# ESP-Power.net
KiCad netlist of a schematic drawn in Altium Designer
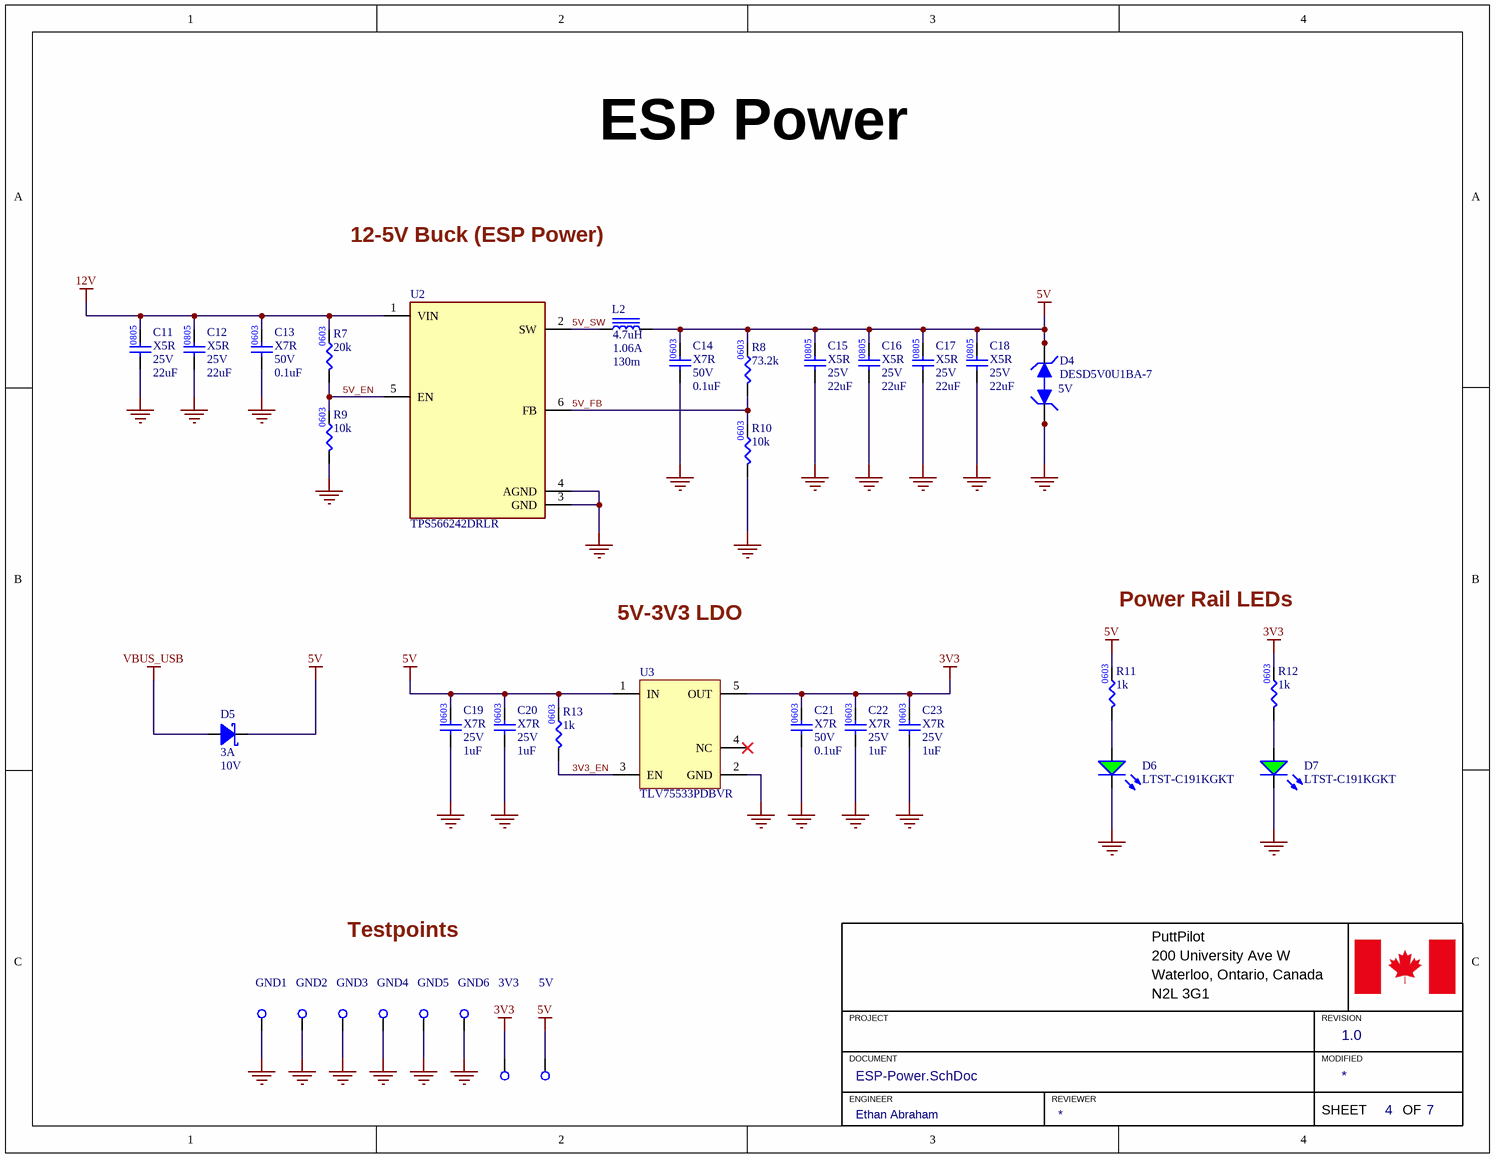
[diagram p0: ESP-Power.SchDoc]

(export (version "E")
  (design (tool "Eeschema 10.0.6"))
  (components
    (comp (ref "3V3")
      (value "RCWCTE")
      (footprint "RCWCTE")
      (description "SMT Test Point")
      (fields (field (name "MANUFACTURER") "KOA Speer"))
      (libsource (lib "PuttPilot") (part "RCWCTE"))
    )
    (comp (ref "5V")
      (value "RCWCTE")
      (footprint "RCWCTE")
      (description "SMT Test Point")
      (fields (field (name "MANUFACTURER") "KOA Speer"))
      (libsource (lib "PuttPilot") (part "RCWCTE"))
    )
    (comp (ref "C11")
      (value "GRM21BR61E226ME44K")
      (footprint ".CAP_0805")
      (description "CAP CER 22uF 25V X5R 0805")
      (fields
        (field (name "MANUFACTURER") "Murata")
        (field (name "TEMPERATURE CHARACTERISTICS CODE") "X5R")
        (field (name "RATED DC VOLTAGE (URDC)") "25V")
        (field (name "CAPACITANCE") "22uF")
      )
      (libsource (lib "PuttPilot") (part "GRM21BR61E226ME44K"))
    )
    (comp (ref "C12")
      (value "GRM21BR61E226ME44K")
      (footprint ".CAP_0805")
      (description "CAP CER 22uF 25V X5R 0805")
      (fields
        (field (name "MANUFACTURER") "Murata")
        (field (name "TEMPERATURE CHARACTERISTICS CODE") "X5R")
        (field (name "RATED DC VOLTAGE (URDC)") "25V")
        (field (name "CAPACITANCE") "22uF")
      )
      (libsource (lib "PuttPilot") (part "GRM21BR61E226ME44K"))
    )
    (comp (ref "C13")
      (value "GCJ188R71H104KA12D")
      (footprint ".CAP_0603")
      (description "CAP CER 0.1uF 50V X7R 0603")
      (fields
        (field (name "MANUFACTURER") "Murata")
        (field (name "TEMPERATURE CHARACTERISTICS CODE") "X7R")
        (field (name "RATED DC VOLTAGE (URDC)") "50V")
        (field (name "CAPACITANCE") "0.1uF")
      )
      (libsource (lib "PuttPilot") (part "GCJ188R71H104KA12D"))
    )
    (comp (ref "C14")
      (value "GCJ188R71H104KA12D")
      (footprint ".CAP_0603")
      (description "CAP CER 0.1uF 50V X7R 0603")
      (fields
        (field (name "MANUFACTURER") "Murata")
        (field (name "TEMPERATURE CHARACTERISTICS CODE") "X7R")
        (field (name "RATED DC VOLTAGE (URDC)") "50V")
        (field (name "CAPACITANCE") "0.1uF")
      )
      (libsource (lib "PuttPilot") (part "GCJ188R71H104KA12D"))
    )
    (comp (ref "C15")
      (value "GRM21BR61E226ME44K")
      (footprint ".CAP_0805")
      (description "CAP CER 22uF 25V X5R 0805")
      (fields
        (field (name "MANUFACTURER") "Murata")
        (field (name "TEMPERATURE CHARACTERISTICS CODE") "X5R")
        (field (name "RATED DC VOLTAGE (URDC)") "25V")
        (field (name "CAPACITANCE") "22uF")
      )
      (libsource (lib "PuttPilot") (part "GRM21BR61E226ME44K"))
    )
    (comp (ref "C16")
      (value "GRM21BR61E226ME44K")
      (footprint ".CAP_0805")
      (description "CAP CER 22uF 25V X5R 0805")
      (fields
        (field (name "MANUFACTURER") "Murata")
        (field (name "TEMPERATURE CHARACTERISTICS CODE") "X5R")
        (field (name "RATED DC VOLTAGE (URDC)") "25V")
        (field (name "CAPACITANCE") "22uF")
      )
      (libsource (lib "PuttPilot") (part "GRM21BR61E226ME44K"))
    )
    (comp (ref "C17")
      (value "GRM21BR61E226ME44K")
      (footprint ".CAP_0805")
      (description "CAP CER 22uF 25V X5R 0805")
      (fields
        (field (name "MANUFACTURER") "Murata")
        (field (name "TEMPERATURE CHARACTERISTICS CODE") "X5R")
        (field (name "RATED DC VOLTAGE (URDC)") "25V")
        (field (name "CAPACITANCE") "22uF")
      )
      (libsource (lib "PuttPilot") (part "GRM21BR61E226ME44K"))
    )
    (comp (ref "C18")
      (value "GRM21BR61E226ME44K")
      (footprint ".CAP_0805")
      (description "CAP CER 22uF 25V X5R 0805")
      (fields
        (field (name "MANUFACTURER") "Murata")
        (field (name "TEMPERATURE CHARACTERISTICS CODE") "X5R")
        (field (name "RATED DC VOLTAGE (URDC)") "25V")
        (field (name "CAPACITANCE") "22uF")
      )
      (libsource (lib "PuttPilot") (part "GRM21BR61E226ME44K"))
    )
    (comp (ref "C19")
      (value "GRT188R71E105KE13D")
      (footprint ".CAP_0603")
      (description "CAP CER 1uF 25V X7R 0603")
      (fields
        (field (name "MANUFACTURER") "Murata")
        (field (name "TEMPERATURE CHARACTERISTICS CODE") "X7R")
        (field (name "RATED DC VOLTAGE (URDC)") "25V")
        (field (name "CAPACITANCE") "1uF")
      )
      (libsource (lib "PuttPilot") (part "GRT188R71E105KE13D"))
    )
    (comp (ref "C20")
      (value "GRT188R71E105KE13D")
      (footprint ".CAP_0603")
      (description "CAP CER 1uF 25V X7R 0603")
      (fields
        (field (name "MANUFACTURER") "Murata")
        (field (name "TEMPERATURE CHARACTERISTICS CODE") "X7R")
        (field (name "RATED DC VOLTAGE (URDC)") "25V")
        (field (name "CAPACITANCE") "1uF")
      )
      (libsource (lib "PuttPilot") (part "GRT188R71E105KE13D"))
    )
    (comp (ref "C21")
      (value "GCJ188R71H104KA12D")
      (footprint ".CAP_0603")
      (description "CAP CER 0.1uF 50V X7R 0603")
      (fields
        (field (name "MANUFACTURER") "Murata")
        (field (name "TEMPERATURE CHARACTERISTICS CODE") "X7R")
        (field (name "RATED DC VOLTAGE (URDC)") "50V")
        (field (name "CAPACITANCE") "0.1uF")
      )
      (libsource (lib "PuttPilot") (part "GCJ188R71H104KA12D"))
    )
    (comp (ref "C22")
      (value "GRT188R71E105KE13D")
      (footprint ".CAP_0603")
      (description "CAP CER 1uF 25V X7R 0603")
      (fields
        (field (name "MANUFACTURER") "Murata")
        (field (name "TEMPERATURE CHARACTERISTICS CODE") "X7R")
        (field (name "RATED DC VOLTAGE (URDC)") "25V")
        (field (name "CAPACITANCE") "1uF")
      )
      (libsource (lib "PuttPilot") (part "GRT188R71E105KE13D"))
    )
    (comp (ref "C23")
      (value "GRT188R71E105KE13D")
      (footprint ".CAP_0603")
      (description "CAP CER 1uF 25V X7R 0603")
      (fields
        (field (name "MANUFACTURER") "Murata")
        (field (name "TEMPERATURE CHARACTERISTICS CODE") "X7R")
        (field (name "RATED DC VOLTAGE (URDC)") "25V")
        (field (name "CAPACITANCE") "1uF")
      )
      (libsource (lib "PuttPilot") (part "GRT188R71E105KE13D"))
    )
    (comp (ref "D4")
      (value "DESD5V0U1BA-7")
      (footprint "DESD5V0U1BA-7")
      (description "TVS DIODE 5VWM")
      (fields (field (name "MANUFACTURER") "Diodes") (field (name "REP PK REVERSE VOLTAGE-MAX") "5V"))
      (libsource (lib "PuttPilot") (part "DESD5V0U1BA-7"))
    )
    (comp (ref "D5")
      (value "BAT60JFILM")
      (footprint "BAT60JFILM")
      (description "DIODE SCHOTTKY 10V 3A SOD323")
      (fields (field (name "MAX CURRENT") "3A") (field (name "MAX VOLTAGE") "10V"))
      (libsource (lib "PuttPilot") (part "BAT60JFILM"))
    )
    (comp (ref "D6")
      (value "LTST-C191KGKT")
      (footprint ".LED_0603")
      (description "LED GREEN 2V 0603")
      (fields (field (name "MANUFACTURER") "Vishay Lite-On"))
      (libsource (lib "PuttPilot") (part "LTST-C191KGKT"))
    )
    (comp (ref "D7")
      (value "LTST-C191KGKT")
      (footprint ".LED_0603")
      (description "LED GREEN 2V 0603")
      (fields (field (name "MANUFACTURER") "Vishay Lite-On"))
      (libsource (lib "PuttPilot") (part "LTST-C191KGKT"))
    )
    (comp (ref "GND1")
      (value "RCWCTE")
      (footprint "RCWCTE")
      (description "SMT Test Point")
      (fields (field (name "MANUFACTURER") "KOA Speer"))
      (libsource (lib "PuttPilot") (part "RCWCTE"))
    )
    (comp (ref "GND2")
      (value "RCWCTE")
      (footprint "RCWCTE")
      (description "SMT Test Point")
      (fields (field (name "MANUFACTURER") "KOA Speer"))
      (libsource (lib "PuttPilot") (part "RCWCTE"))
    )
    (comp (ref "GND3")
      (value "RCWCTE")
      (footprint "RCWCTE")
      (description "SMT Test Point")
      (fields (field (name "MANUFACTURER") "KOA Speer"))
      (libsource (lib "PuttPilot") (part "RCWCTE"))
    )
    (comp (ref "GND4")
      (value "RCWCTE")
      (footprint "RCWCTE")
      (description "SMT Test Point")
      (fields (field (name "MANUFACTURER") "KOA Speer"))
      (libsource (lib "PuttPilot") (part "RCWCTE"))
    )
    (comp (ref "GND5")
      (value "RCWCTE")
      (footprint "RCWCTE")
      (description "SMT Test Point")
      (fields (field (name "MANUFACTURER") "KOA Speer"))
      (libsource (lib "PuttPilot") (part "RCWCTE"))
    )
    (comp (ref "GND6")
      (value "RCWCTE")
      (footprint "RCWCTE")
      (description "SMT Test Point")
      (fields (field (name "MANUFACTURER") "KOA Speer"))
      (libsource (lib "PuttPilot") (part "RCWCTE"))
    )
    (comp (ref "L2")
      (value "NRH3012T4R7MN")
      (footprint "NRH3012T4R7MN")
      (description "FIXED IND 4.7uH 1.06A")
      (fields
        (field (name "MANUFACTURER") "Taiyo Yuden")
        (field (name "TOLERANCE") "20%")
        (field (name "DC RESISTANCE (DCR)") "130m")
        (field (name "INDUCTANCE-NOM (L)") "4.7uH")
        (field (name "RATED CURRENT-MAX") "1.06A")
      )
      (libsource (lib "PuttPilot") (part "NRH3012T4R7MN"))
    )
    (comp (ref "R7")
      (value "ERJ-3EKF2002V")
      (footprint ".RES_0603")
      (description "RES 20K OHM 0603")
      (fields
        (field (name "MANUFACTURER") "Panasonic")
        (field (name "TOLERANCE") "1%")
        (field (name "RESISTANCE") "20k")
      )
      (libsource (lib "PuttPilot") (part "ERJ-3EKF2002V"))
    )
    (comp (ref "R8")
      (value "RC0603FR-0773K2L")
      (footprint ".RES_0603")
      (description "RES 73.2K OHM 0603")
      (fields
        (field (name "MANUFACTURER") "Yageo")
        (field (name "TOLERANCE") "1%")
        (field (name "RESISTANCE") "73.2k")
      )
      (libsource (lib "PuttPilot") (part "RC0603FR-0773K2L"))
    )
    (comp (ref "R9")
      (value "RC0603FR-0710KL")
      (footprint ".RES_0603")
      (description "RES 10K OHM 0603")
      (fields
        (field (name "MANUFACTURER") "Yageo")
        (field (name "TOLERANCE") "1%")
        (field (name "RESISTANCE") "10k")
      )
      (libsource (lib "PuttPilot") (part "RC0603FR-0710KL"))
    )
    (comp (ref "R10")
      (value "RC0603FR-0710KL")
      (footprint ".RES_0603")
      (description "RES 10K OHM 0603")
      (fields
        (field (name "MANUFACTURER") "Yageo")
        (field (name "TOLERANCE") "1%")
        (field (name "RESISTANCE") "10k")
      )
      (libsource (lib "PuttPilot") (part "RC0603FR-0710KL"))
    )
    (comp (ref "R11")
      (value "RC0603FR-071KL")
      (footprint ".RES_0603")
      (description "RES 1K OHM 0603")
      (fields
        (field (name "MANUFACTURER") "Yageo")
        (field (name "TOLERANCE") "1%")
        (field (name "RESISTANCE") "1k")
      )
      (libsource (lib "PuttPilot") (part "RC0603FR-071KL"))
    )
    (comp (ref "R12")
      (value "RC0603FR-071KL")
      (footprint ".RES_0603")
      (description "RES 1K OHM 0603")
      (fields
        (field (name "MANUFACTURER") "Yageo")
        (field (name "TOLERANCE") "1%")
        (field (name "RESISTANCE") "1k")
      )
      (libsource (lib "PuttPilot") (part "RC0603FR-071KL"))
    )
    (comp (ref "R13")
      (value "RC0603FR-071KL")
      (footprint ".RES_0603")
      (description "RES 1K OHM 0603")
      (fields
        (field (name "MANUFACTURER") "Yageo")
        (field (name "TOLERANCE") "1%")
        (field (name "RESISTANCE") "1k")
      )
      (libsource (lib "PuttPilot") (part "RC0603FR-071KL"))
    )
    (comp (ref "U2")
      (value "TPS566242DRLR")
      (footprint "TPS566242DRLR")
      (description "BUCK 3V-16V 6A SOT-563")
      (fields (field (name "MANUFACTURER") "Texas Instruments"))
      (libsource (lib "PuttPilot") (part "TPS566242DRLR"))
    )
    (comp (ref "U3")
      (value "TLV75533PDBVR")
      (footprint ".SOT-23-5")
      (description "3V3 (Fixed) LDO 500mA SOT25")
      (fields (field (name "MANUFACTURER") "Texas Instruments"))
      (libsource (lib "PuttPilot") (part "TLV75533PDBVR"))
    )
  )
  (nets
    (net (code "1") (name "/3V3_EN") (class "Default")
      (node (ref "R13") (pin "1") (pinfunction "1_1") (pintype "passive"))
      (node (ref "U3") (pin "3") (pinfunction "EN_3") (pintype "passive"))
    )
    (net (code "2") (name "/5V_EN") (class "Default")
      (node (ref "R7") (pin "1") (pinfunction "1_1") (pintype "passive"))
      (node (ref "R9") (pin "2") (pinfunction "2_2") (pintype "passive"))
      (node (ref "U2") (pin "5") (pinfunction "EN_5") (pintype "passive"))
    )
    (net (code "3") (name "/5V_FB") (class "Default")
      (node (ref "R10") (pin "2") (pinfunction "2_2") (pintype "passive"))
      (node (ref "R8") (pin "1") (pinfunction "1_1") (pintype "passive"))
      (node (ref "U2") (pin "6") (pinfunction "FB_6") (pintype "passive"))
    )
    (net (code "4") (name "/5V_SW") (class "Default")
      (node (ref "L2") (pin "1") (pinfunction "1_1") (pintype "passive"))
      (node (ref "U2") (pin "2") (pinfunction "SW_2") (pintype "passive"))
    )
    (net (code "5") (name "3V3") (class "Default")
      (node (ref "3V3") (pin "1") (pinfunction "1_1") (pintype "passive"))
      (node (ref "C21") (pin "2") (pinfunction "2_2") (pintype "passive"))
      (node (ref "C22") (pin "2") (pinfunction "2_2") (pintype "passive"))
      (node (ref "C23") (pin "2") (pinfunction "2_2") (pintype "passive"))
      (node (ref "R12") (pin "2") (pinfunction "2_2") (pintype "passive"))
      (node (ref "U3") (pin "5") (pinfunction "OUT_5") (pintype "passive"))
    )
    (net (code "6") (name "5V") (class "Default")
      (node (ref "5V") (pin "1") (pinfunction "1_1") (pintype "passive"))
      (node (ref "C14") (pin "2") (pinfunction "2_2") (pintype "passive"))
      (node (ref "C15") (pin "2") (pinfunction "2_2") (pintype "passive"))
      (node (ref "C16") (pin "2") (pinfunction "2_2") (pintype "passive"))
      (node (ref "C17") (pin "2") (pinfunction "2_2") (pintype "passive"))
      (node (ref "C18") (pin "2") (pinfunction "2_2") (pintype "passive"))
      (node (ref "C19") (pin "2") (pinfunction "2_2") (pintype "passive"))
      (node (ref "C20") (pin "2") (pinfunction "2_2") (pintype "passive"))
      (node (ref "D4") (pin "2") (pinfunction "Pin_2_2") (pintype "passive"))
      (node (ref "D5") (pin "2") (pinfunction "Cathode_2") (pintype "passive"))
      (node (ref "L2") (pin "2") (pinfunction "2_2") (pintype "passive"))
      (node (ref "R11") (pin "2") (pinfunction "2_2") (pintype "passive"))
      (node (ref "R13") (pin "2") (pinfunction "2_2") (pintype "passive"))
      (node (ref "R8") (pin "2") (pinfunction "2_2") (pintype "passive"))
      (node (ref "U3") (pin "1") (pinfunction "IN_1") (pintype "passive"))
    )
    (net (code "7") (name "12V") (class "Default")
      (node (ref "C11") (pin "2") (pinfunction "2_2") (pintype "passive"))
      (node (ref "C12") (pin "2") (pinfunction "2_2") (pintype "passive"))
      (node (ref "C13") (pin "2") (pinfunction "2_2") (pintype "passive"))
      (node (ref "R7") (pin "2") (pinfunction "2_2") (pintype "passive"))
      (node (ref "U2") (pin "1") (pinfunction "VIN_1") (pintype "passive"))
    )
    (net (code "8") (name "GND") (class "Default")
      (node (ref "C11") (pin "1") (pinfunction "1_1") (pintype "passive"))
      (node (ref "C12") (pin "1") (pinfunction "1_1") (pintype "passive"))
      (node (ref "C13") (pin "1") (pinfunction "1_1") (pintype "passive"))
      (node (ref "C14") (pin "1") (pinfunction "1_1") (pintype "passive"))
      (node (ref "C15") (pin "1") (pinfunction "1_1") (pintype "passive"))
      (node (ref "C16") (pin "1") (pinfunction "1_1") (pintype "passive"))
      (node (ref "C17") (pin "1") (pinfunction "1_1") (pintype "passive"))
      (node (ref "C18") (pin "1") (pinfunction "1_1") (pintype "passive"))
      (node (ref "C19") (pin "1") (pinfunction "1_1") (pintype "passive"))
      (node (ref "C20") (pin "1") (pinfunction "1_1") (pintype "passive"))
      (node (ref "C21") (pin "1") (pinfunction "1_1") (pintype "passive"))
      (node (ref "C22") (pin "1") (pinfunction "1_1") (pintype "passive"))
      (node (ref "C23") (pin "1") (pinfunction "1_1") (pintype "passive"))
      (node (ref "D4") (pin "1") (pinfunction "Pin_1_1") (pintype "passive"))
      (node (ref "D6") (pin "2") (pinfunction "K_2") (pintype "passive"))
      (node (ref "D7") (pin "2") (pinfunction "K_2") (pintype "passive"))
      (node (ref "GND1") (pin "1") (pinfunction "1_1") (pintype "passive"))
      (node (ref "GND2") (pin "1") (pinfunction "1_1") (pintype "passive"))
      (node (ref "GND3") (pin "1") (pinfunction "1_1") (pintype "passive"))
      (node (ref "GND4") (pin "1") (pinfunction "1_1") (pintype "passive"))
      (node (ref "GND5") (pin "1") (pinfunction "1_1") (pintype "passive"))
      (node (ref "GND6") (pin "1") (pinfunction "1_1") (pintype "passive"))
      (node (ref "R10") (pin "1") (pinfunction "1_1") (pintype "passive"))
      (node (ref "R9") (pin "1") (pinfunction "1_1") (pintype "passive"))
      (node (ref "U2") (pin "3") (pinfunction "GND_3") (pintype "passive"))
      (node (ref "U2") (pin "4") (pinfunction "AGND_4") (pintype "passive"))
      (node (ref "U3") (pin "2") (pinfunction "GND_2") (pintype "passive"))
    )
    (net (code "9") (name "Net-(D6-A)") (class "Default")
      (node (ref "D6") (pin "1") (pinfunction "A_1") (pintype "passive"))
      (node (ref "R11") (pin "1") (pinfunction "1_1") (pintype "passive"))
    )
    (net (code "10") (name "Net-(D7-A)") (class "Default")
      (node (ref "D7") (pin "1") (pinfunction "A_1") (pintype "passive"))
      (node (ref "R12") (pin "1") (pinfunction "1_1") (pintype "passive"))
    )
    (net (code "11") (name "VBUS_USB") (class "Default")
      (node (ref "D5") (pin "1") (pinfunction "Anode_1") (pintype "passive"))
    )
    (net (code "12") (name "unconnected-(U3-NC-Pad4)") (class "Default")
      (node (ref "U3") (pin "4") (pinfunction "NC_4") (pintype "passive+no_connect"))
    )
  )
)
